# Audio_Board_REV_A.net
KiCad netlist of a schematic drawn in EAGLE
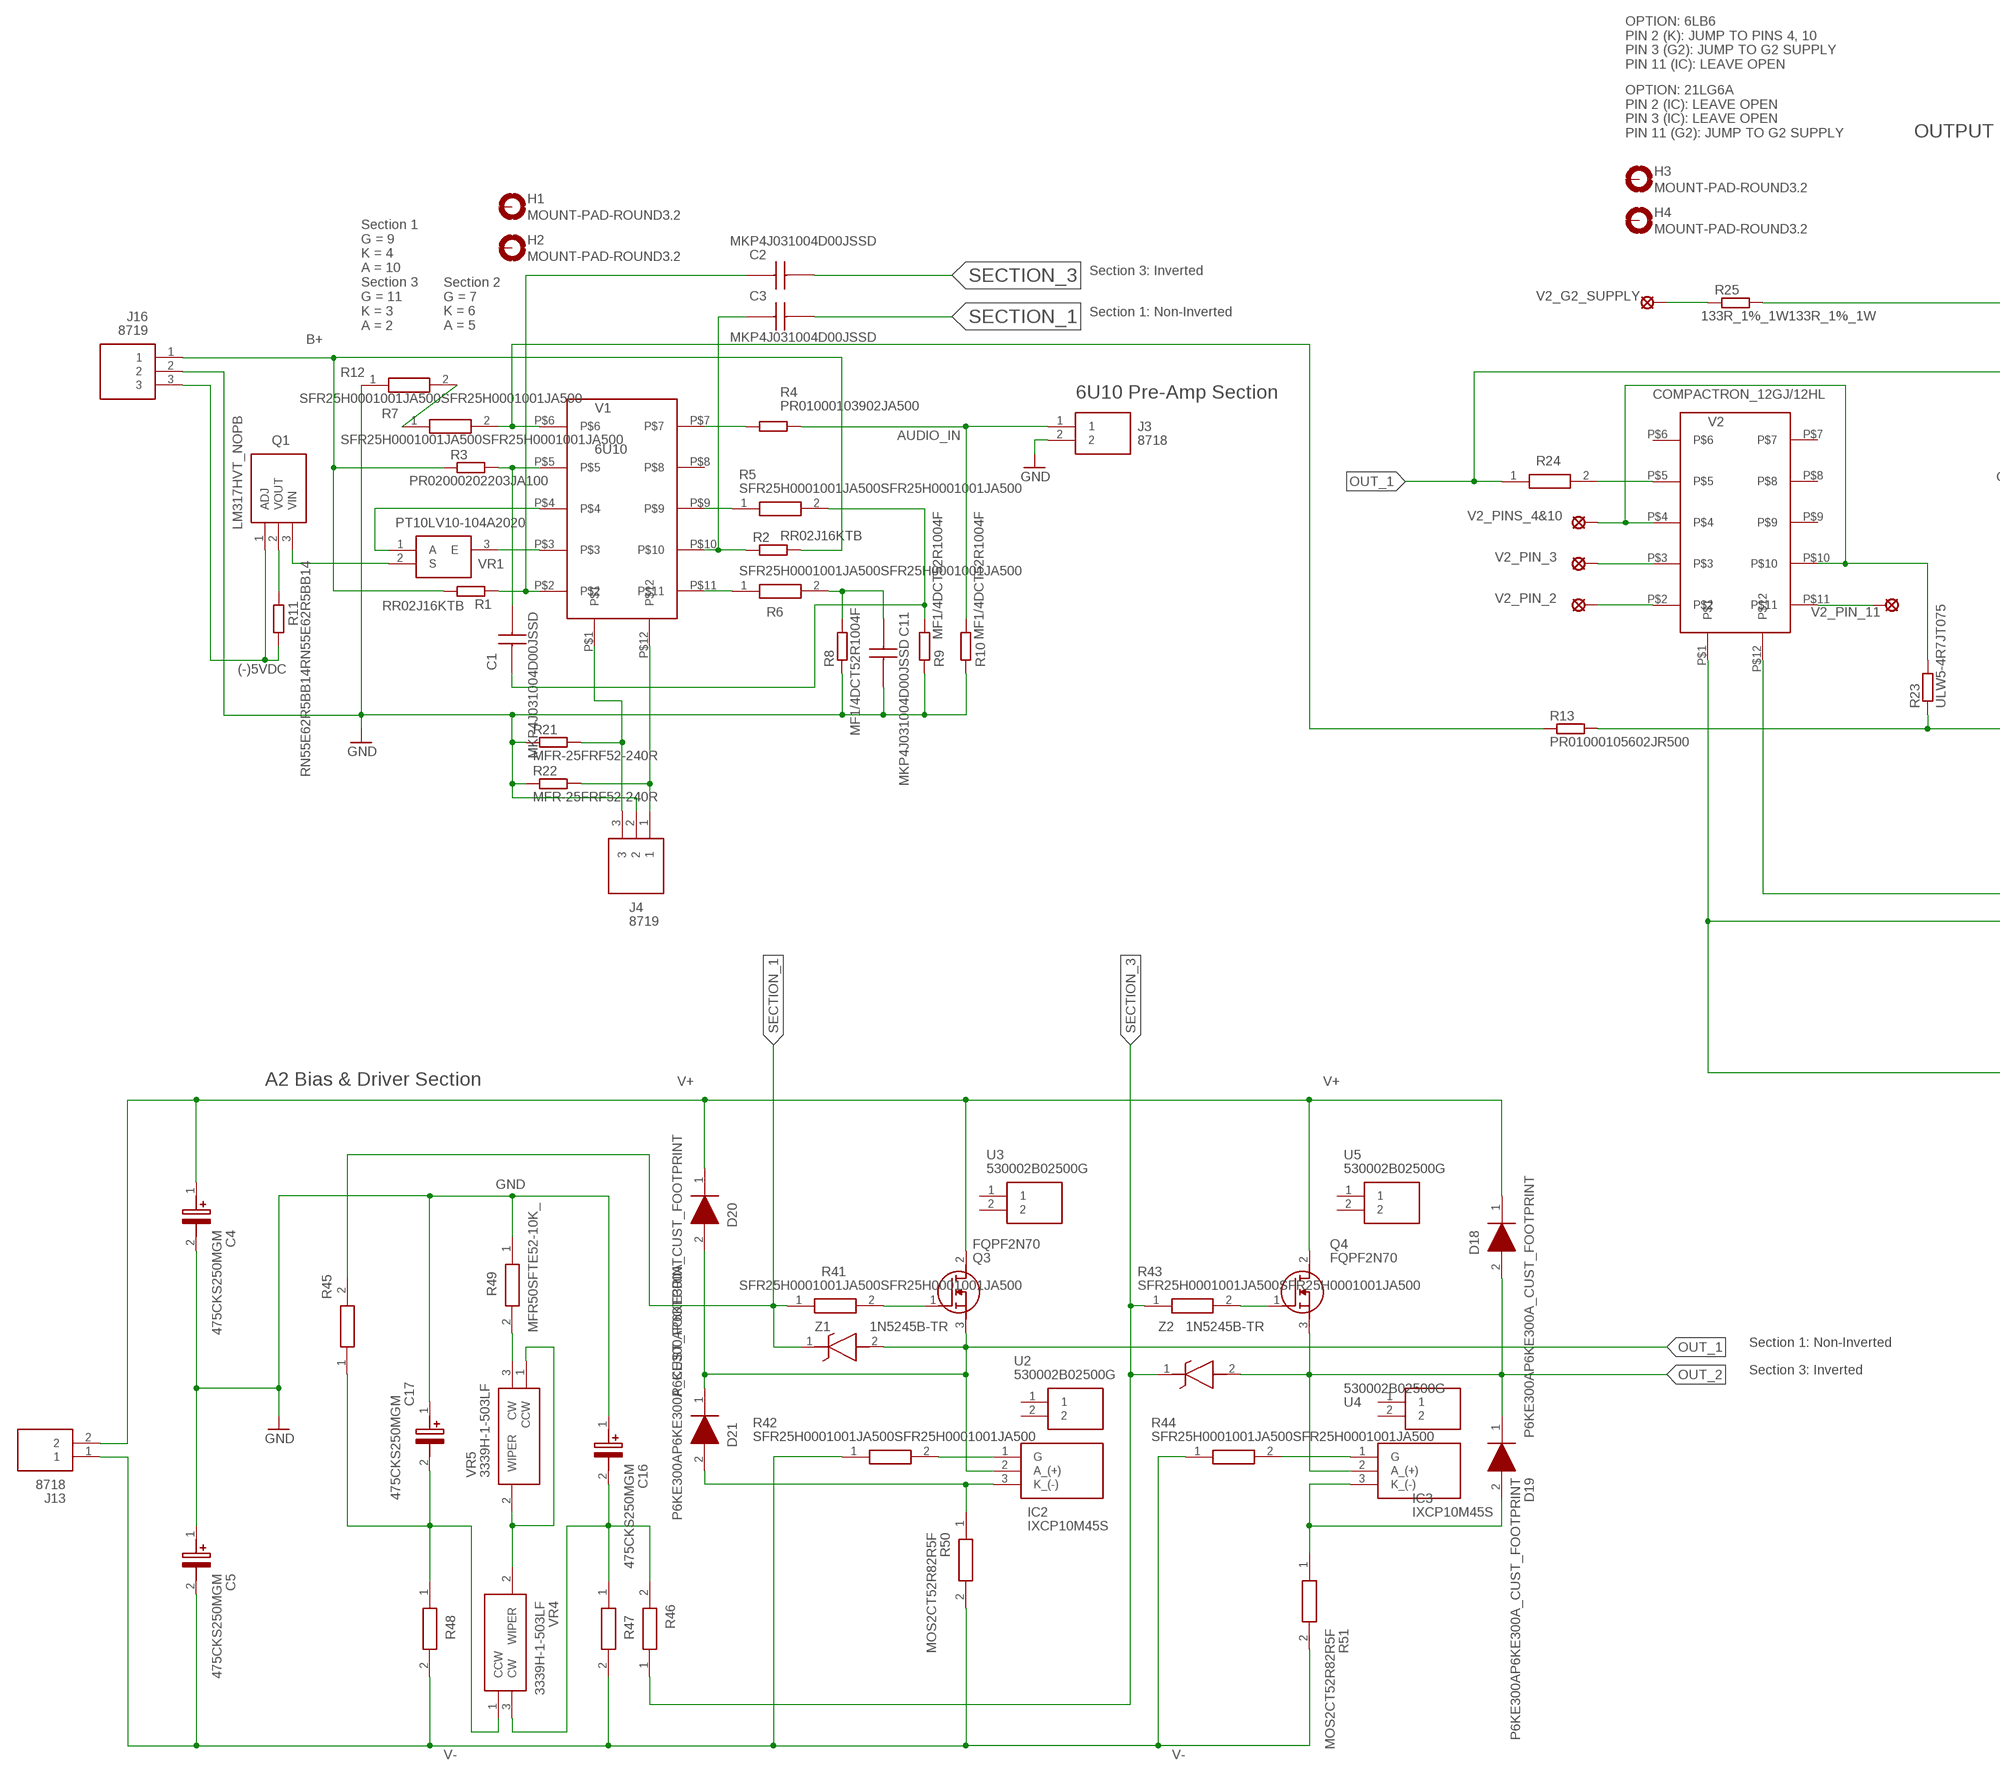
[diagram p0: schematic, sheet 1, part 1 of 2]
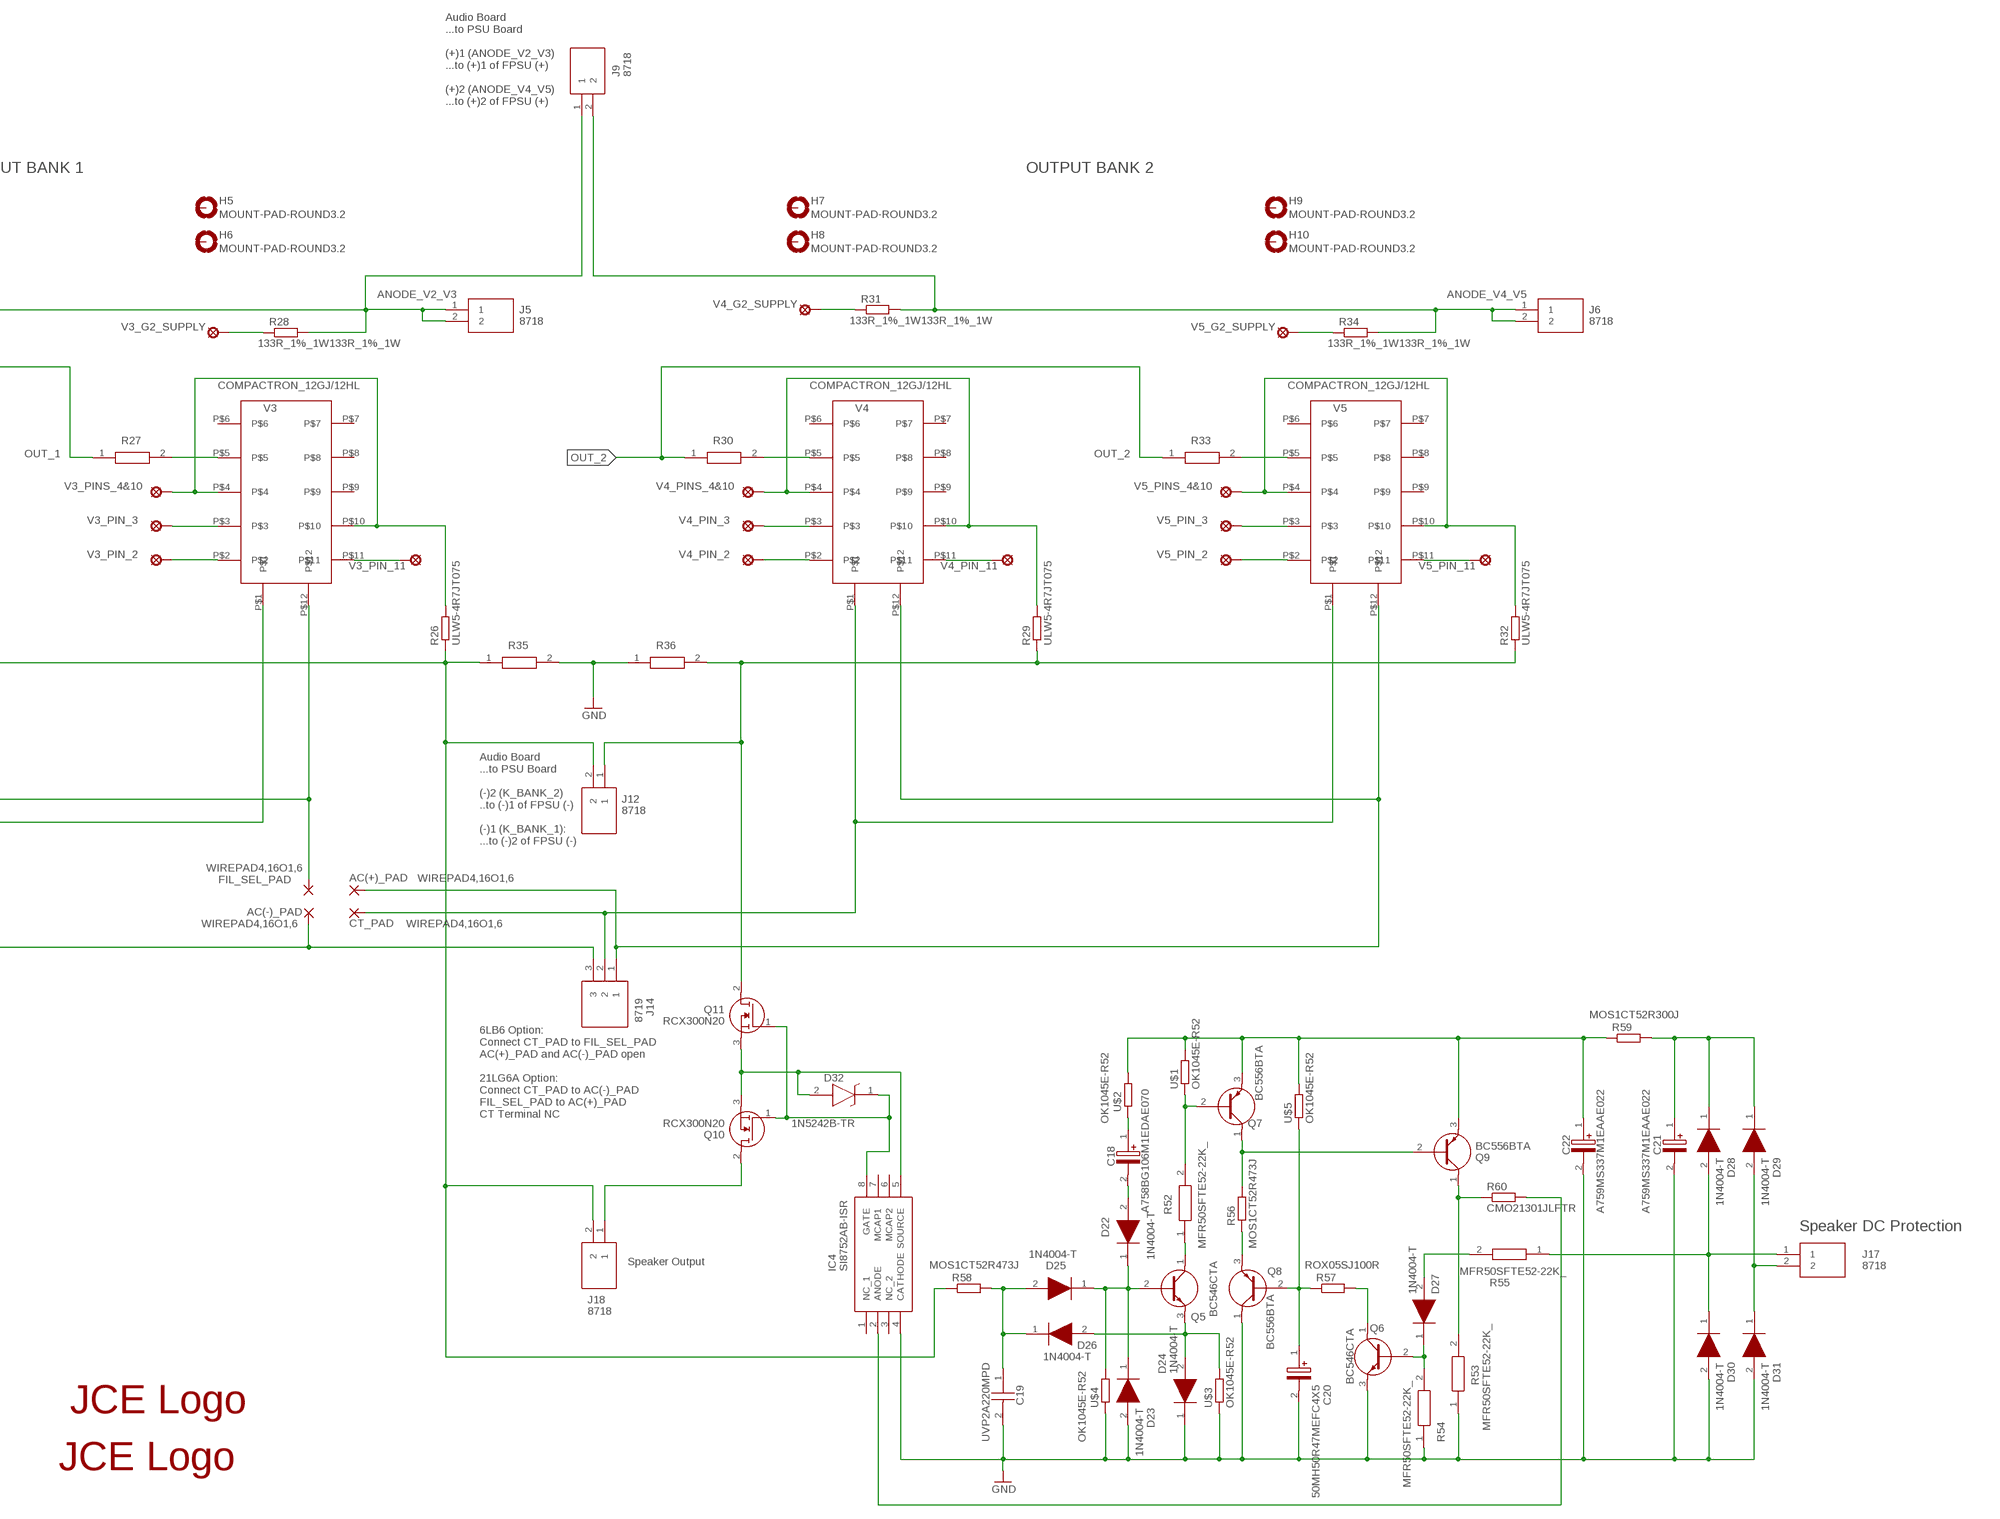
[diagram p1: schematic, sheet 1, part 2 of 2]

(export (version "E")
  (design (tool "Eeschema 10.0.6"))
  (components
    (comp (ref "AC(+)_PAD")
      (value "WIREPAD4,16O1,6")
      (footprint "eagle-import:4,16O1,6")
      (libsource (lib "eagle-import") (part "WIREPAD4,16O1,6"))
    )
    (comp (ref "AC(-)_PAD")
      (value "WIREPAD4,16O1,6")
      (footprint "eagle-import:4,16O1,6")
      (libsource (lib "eagle-import") (part "WIREPAD4,16O1,6"))
    )
    (comp (ref "C1")
      (value "MKP4J031004D00JSSD")
      (footprint "eagle-import:MKP4J031004D00_")
      (libsource (lib "eagle-import") (part "MKP4J031004D00JSSD"))
    )
    (comp (ref "C2")
      (value "MKP4J031004D00JSSD")
      (footprint "eagle-import:MKP4J031004D00_")
      (libsource (lib "eagle-import") (part "MKP4J031004D00JSSD"))
    )
    (comp (ref "C3")
      (value "MKP4J031004D00JSSD")
      (footprint "eagle-import:MKP4J031004D00_")
      (libsource (lib "eagle-import") (part "MKP4J031004D00JSSD"))
    )
    (comp (ref "C4")
      (value "475CKS250MGM")
      (footprint "eagle-import:CAPPRD250W55D655H1250")
      (libsource (lib "eagle-import") (part "475CKS250MGM"))
    )
    (comp (ref "C5")
      (value "475CKS250MGM")
      (footprint "eagle-import:CAPPRD250W55D655H1250")
      (libsource (lib "eagle-import") (part "475CKS250MGM"))
    )
    (comp (ref "C11")
      (value "MKP4J031004D00JSSD")
      (footprint "eagle-import:MKP4J031004D00_")
      (libsource (lib "eagle-import") (part "MKP4J031004D00JSSD"))
    )
    (comp (ref "C16")
      (value "475CKS250MGM")
      (footprint "eagle-import:CAPPRD250W55D655H1250")
      (libsource (lib "eagle-import") (part "475CKS250MGM"))
    )
    (comp (ref "C17")
      (value "475CKS250MGM")
      (footprint "eagle-import:CAPPRD250W55D655H1250")
      (libsource (lib "eagle-import") (part "475CKS250MGM"))
    )
    (comp (ref "C18")
      (value "A758BG106M1EDAE070")
      (footprint "eagle-import:CAPPRD200W55D500H800")
      (fields (field (name "MOUSER_PART_NUMBER") "80-A758BG106M1EDAE70"))
      (libsource (lib "eagle-import") (part "A758BG106M1EDAE070"))
    )
    (comp (ref "C19")
      (value "UVP2A220MPD")
      (footprint "eagle-import:CAPPRD500W60D1025H1750")
      (libsource (lib "eagle-import") (part "UVP2A220MPD"))
    )
    (comp (ref "C20")
      (value "50MH50R47MEFC4X5")
      (footprint "eagle-import:CAPPRD150W45D425H650")
      (libsource (lib "eagle-import") (part "50MH50R47MEFC4X5"))
    )
    (comp (ref "C21")
      (value "A759MS337M1EAAE022")
      (footprint "eagle-import:CAPPRD500W65D1000H1300")
      (libsource (lib "eagle-import") (part "A759MS337M1EAAE022"))
    )
    (comp (ref "C22")
      (value "A759MS337M1EAAE022")
      (footprint "eagle-import:CAPPRD500W65D1000H1300")
      (libsource (lib "eagle-import") (part "A759MS337M1EAAE022"))
    )
    (comp (ref "CT_PAD")
      (value "WIREPAD4,16O1,6")
      (footprint "eagle-import:4,16O1,6")
      (libsource (lib "eagle-import") (part "WIREPAD4,16O1,6"))
    )
    (comp (ref "D18")
      (value "P6KE300AP6KE300A_CUST_FOOTPRINT")
      (footprint "eagle-import:DIOAD1299W88L640D324B")
      (libsource (lib "eagle-import") (part "P6KE300AP6KE300A_CUST_FOOTPRINT"))
    )
    (comp (ref "D19")
      (value "P6KE300AP6KE300A_CUST_FOOTPRINT")
      (footprint "eagle-import:DIOAD1299W88L640D324B")
      (libsource (lib "eagle-import") (part "P6KE300AP6KE300A_CUST_FOOTPRINT"))
    )
    (comp (ref "D20")
      (value "P6KE300AP6KE300A_CUST_FOOTPRINT")
      (footprint "eagle-import:DIOAD1299W88L640D324B")
      (libsource (lib "eagle-import") (part "P6KE300AP6KE300A_CUST_FOOTPRINT"))
    )
    (comp (ref "D21")
      (value "P6KE300AP6KE300A_CUST_FOOTPRINT")
      (footprint "eagle-import:DIOAD1299W88L640D324B")
      (libsource (lib "eagle-import") (part "P6KE300AP6KE300A_CUST_FOOTPRINT"))
    )
    (comp (ref "D22")
      (value "1N4004-T")
      (footprint "eagle-import:DIOAD1408W86L464D236")
      (fields (field (name "MOUSER_PART_NUMBER") "621-1N4004"))
      (libsource (lib "eagle-import") (part "1N4004-T"))
    )
    (comp (ref "D23")
      (value "1N4004-T")
      (footprint "eagle-import:DIOAD1408W86L464D236")
      (fields (field (name "MOUSER_PART_NUMBER") "621-1N4004"))
      (libsource (lib "eagle-import") (part "1N4004-T"))
    )
    (comp (ref "D24")
      (value "1N4004-T")
      (footprint "eagle-import:DIOAD1408W86L464D236")
      (fields (field (name "MOUSER_PART_NUMBER") "621-1N4004"))
      (libsource (lib "eagle-import") (part "1N4004-T"))
    )
    (comp (ref "D25")
      (value "1N4004-T")
      (footprint "eagle-import:DIOAD1408W86L464D236")
      (fields (field (name "MOUSER_PART_NUMBER") "621-1N4004"))
      (libsource (lib "eagle-import") (part "1N4004-T"))
    )
    (comp (ref "D26")
      (value "1N4004-T")
      (footprint "eagle-import:DIOAD1408W86L464D236")
      (fields (field (name "MOUSER_PART_NUMBER") "621-1N4004"))
      (libsource (lib "eagle-import") (part "1N4004-T"))
    )
    (comp (ref "D27")
      (value "1N4004-T")
      (footprint "eagle-import:DIOAD1408W86L464D236")
      (fields (field (name "MOUSER_PART_NUMBER") "621-1N4004"))
      (libsource (lib "eagle-import") (part "1N4004-T"))
    )
    (comp (ref "D28")
      (value "1N4004-T")
      (footprint "eagle-import:DIOAD1408W86L464D236")
      (fields (field (name "MOUSER_PART_NUMBER") "621-1N4004"))
      (libsource (lib "eagle-import") (part "1N4004-T"))
    )
    (comp (ref "D29")
      (value "1N4004-T")
      (footprint "eagle-import:DIOAD1408W86L464D236")
      (fields (field (name "MOUSER_PART_NUMBER") "621-1N4004"))
      (libsource (lib "eagle-import") (part "1N4004-T"))
    )
    (comp (ref "D30")
      (value "1N4004-T")
      (footprint "eagle-import:DIOAD1408W86L464D236")
      (fields (field (name "MOUSER_PART_NUMBER") "621-1N4004"))
      (libsource (lib "eagle-import") (part "1N4004-T"))
    )
    (comp (ref "D31")
      (value "1N4004-T")
      (footprint "eagle-import:DIOAD1408W86L464D236")
      (fields (field (name "MOUSER_PART_NUMBER") "621-1N4004"))
      (libsource (lib "eagle-import") (part "1N4004-T"))
    )
    (comp (ref "D32")
      (value "1N5242B-TR")
      (footprint "eagle-import:DIOAD700W55L350D160B")
      (libsource (lib "eagle-import") (part "1N5242B-TR"))
    )
    (comp (ref "FIL_SEL_PAD")
      (value "WIREPAD4,16O1,6")
      (footprint "eagle-import:4,16O1,6")
      (libsource (lib "eagle-import") (part "WIREPAD4,16O1,6"))
    )
    (comp (ref "H1")
      (value "MOUNT-PAD-ROUND3.2")
      (footprint "eagle-import:3,2-PAD")
      (libsource (lib "eagle-import") (part "MOUNT-PAD-ROUND3.2"))
    )
    (comp (ref "H2")
      (value "MOUNT-PAD-ROUND3.2")
      (footprint "eagle-import:3,2-PAD")
      (libsource (lib "eagle-import") (part "MOUNT-PAD-ROUND3.2"))
    )
    (comp (ref "H3")
      (value "MOUNT-PAD-ROUND3.2")
      (footprint "eagle-import:3,2-PAD")
      (libsource (lib "eagle-import") (part "MOUNT-PAD-ROUND3.2"))
    )
    (comp (ref "H4")
      (value "MOUNT-PAD-ROUND3.2")
      (footprint "eagle-import:3,2-PAD")
      (libsource (lib "eagle-import") (part "MOUNT-PAD-ROUND3.2"))
    )
    (comp (ref "H5")
      (value "MOUNT-PAD-ROUND3.2")
      (footprint "eagle-import:3,2-PAD")
      (libsource (lib "eagle-import") (part "MOUNT-PAD-ROUND3.2"))
    )
    (comp (ref "H6")
      (value "MOUNT-PAD-ROUND3.2")
      (footprint "eagle-import:3,2-PAD")
      (libsource (lib "eagle-import") (part "MOUNT-PAD-ROUND3.2"))
    )
    (comp (ref "H7")
      (value "MOUNT-PAD-ROUND3.2")
      (footprint "eagle-import:3,2-PAD")
      (libsource (lib "eagle-import") (part "MOUNT-PAD-ROUND3.2"))
    )
    (comp (ref "H8")
      (value "MOUNT-PAD-ROUND3.2")
      (footprint "eagle-import:3,2-PAD")
      (libsource (lib "eagle-import") (part "MOUNT-PAD-ROUND3.2"))
    )
    (comp (ref "H9")
      (value "MOUNT-PAD-ROUND3.2")
      (footprint "eagle-import:3,2-PAD")
      (libsource (lib "eagle-import") (part "MOUNT-PAD-ROUND3.2"))
    )
    (comp (ref "H10")
      (value "MOUNT-PAD-ROUND3.2")
      (footprint "eagle-import:3,2-PAD")
      (libsource (lib "eagle-import") (part "MOUNT-PAD-ROUND3.2"))
    )
    (comp (ref "IC2")
      (value "IXCP10M45S")
      (footprint "eagle-import:TO254P482X1016X2386-3P")
      (fields (field (name "MOUSER_PART_NUMBER") "747-IXCP10M45S"))
      (libsource (lib "eagle-import") (part "IXCP10M45S"))
    )
    (comp (ref "IC3")
      (value "IXCP10M45S")
      (footprint "eagle-import:TO254P482X1016X2386-3P")
      (fields (field (name "MOUSER_PART_NUMBER") "747-IXCP10M45S"))
      (libsource (lib "eagle-import") (part "IXCP10M45S"))
    )
    (comp (ref "IC4")
      (value "SI8752AB-ISR")
      (footprint "eagle-import:SOIC127P600X175-8N")
      (fields (field (name "MOUSER_PART_NUMBER") "634-SI8752AB-ISR"))
      (libsource (lib "eagle-import") (part "SI8752AB-ISR"))
    )
    (comp (ref "J3")
      (value "8718")
      (footprint "eagle-import:SHDR2W99P0X500_1X2_1001X762X10")
      (fields (field (name "MOUSER_PART_NUMBER") "534-8718"))
      (libsource (lib "eagle-import") (part "8718"))
    )
    (comp (ref "J4")
      (value "8719")
      (footprint "eagle-import:8719")
      (fields (field (name "MOUSER_PART_NUMBER") "534-8719"))
      (libsource (lib "eagle-import") (part "8719"))
    )
    (comp (ref "J5")
      (value "8718")
      (footprint "eagle-import:SHDR2W99P0X500_1X2_1001X762X10")
      (fields (field (name "MOUSER_PART_NUMBER") "534-8718"))
      (libsource (lib "eagle-import") (part "8718"))
    )
    (comp (ref "J6")
      (value "8718")
      (footprint "eagle-import:SHDR2W99P0X500_1X2_1001X762X10")
      (fields (field (name "MOUSER_PART_NUMBER") "534-8718"))
      (libsource (lib "eagle-import") (part "8718"))
    )
    (comp (ref "J9")
      (value "8718")
      (footprint "eagle-import:SHDR2W99P0X500_1X2_1001X762X10")
      (fields (field (name "MOUSER_PART_NUMBER") "534-8718"))
      (libsource (lib "eagle-import") (part "8718"))
    )
    (comp (ref "J12")
      (value "8718")
      (footprint "eagle-import:SHDR2W99P0X500_1X2_1001X762X10")
      (fields (field (name "MOUSER_PART_NUMBER") "534-8718"))
      (libsource (lib "eagle-import") (part "8718"))
    )
    (comp (ref "J13")
      (value "8718")
      (footprint "eagle-import:SHDR2W99P0X500_1X2_1001X762X10")
      (fields (field (name "MOUSER_PART_NUMBER") "534-8718"))
      (libsource (lib "eagle-import") (part "8718"))
    )
    (comp (ref "J14")
      (value "8719")
      (footprint "eagle-import:8719")
      (fields (field (name "MOUSER_PART_NUMBER") "534-8719"))
      (libsource (lib "eagle-import") (part "8719"))
    )
    (comp (ref "J16")
      (value "8719")
      (footprint "eagle-import:8719")
      (fields (field (name "MOUSER_PART_NUMBER") "534-8719"))
      (libsource (lib "eagle-import") (part "8719"))
    )
    (comp (ref "J17")
      (value "8718")
      (footprint "eagle-import:SHDR2W99P0X500_1X2_1001X762X10")
      (fields (field (name "MOUSER_PART_NUMBER") "534-8718"))
      (libsource (lib "eagle-import") (part "8718"))
    )
    (comp (ref "J18")
      (value "8718")
      (footprint "eagle-import:SHDR2W99P0X500_1X2_1001X762X10")
      (fields (field (name "MOUSER_PART_NUMBER") "534-8718"))
      (libsource (lib "eagle-import") (part "8718"))
    )
    (comp (ref "Q1")
      (value "LM317HVT_NOPB")
      (footprint "eagle-import:TO254P470X1028X1955-3P")
      (fields
        (field (name "MANUFACTURER_PART_NUMBER") "LM317HVT/NOPB")
        (field (name "MOUSER_PART_NUMBER") "926-LM317HVT/NOPB")
      )
      (libsource (lib "eagle-import") (part "LM317HVT_NOPB"))
    )
    (comp (ref "Q3")
      (value "FQPF2N70")
      (footprint "eagle-import:TO254P490X1016X1977-3P")
      (libsource (lib "eagle-import") (part "FQPF2N70"))
    )
    (comp (ref "Q4")
      (value "FQPF2N70")
      (footprint "eagle-import:TO254P490X1016X1977-3P")
      (libsource (lib "eagle-import") (part "FQPF2N70"))
    )
    (comp (ref "Q5")
      (value "BC546CTA")
      (footprint "eagle-import:KA431AZTA")
      (fields (field (name "MOUSER_PART_NUMBER") "512-BC546CTA"))
      (libsource (lib "eagle-import") (part "BC546CTA"))
    )
    (comp (ref "Q6")
      (value "BC546CTA")
      (footprint "eagle-import:KA431AZTA")
      (fields (field (name "MOUSER_PART_NUMBER") "512-BC546CTA"))
      (libsource (lib "eagle-import") (part "BC546CTA"))
    )
    (comp (ref "Q7")
      (value "BC556BTA")
      (footprint "eagle-import:BC33740TA")
      (fields (field (name "MOUSER_PART_NUMBER") "512-BC556BTA"))
      (libsource (lib "eagle-import") (part "BC556BTA"))
    )
    (comp (ref "Q8")
      (value "BC556BTA")
      (footprint "eagle-import:BC33740TA")
      (fields (field (name "MOUSER_PART_NUMBER") "512-BC556BTA"))
      (libsource (lib "eagle-import") (part "BC556BTA"))
    )
    (comp (ref "Q9")
      (value "BC556BTA")
      (footprint "eagle-import:BC33740TA")
      (fields (field (name "MOUSER_PART_NUMBER") "512-BC556BTA"))
      (libsource (lib "eagle-import") (part "BC556BTA"))
    )
    (comp (ref "Q10")
      (value "RCX300N20")
      (footprint "eagle-import:TO254P480X1010X1760-3P")
      (libsource (lib "eagle-import") (part "RCX300N20"))
    )
    (comp (ref "Q11")
      (value "RCX300N20")
      (footprint "eagle-import:TO254P480X1010X1760-3P")
      (libsource (lib "eagle-import") (part "RCX300N20"))
    )
    (comp (ref "R1")
      (value "RR02J16KTB")
      (footprint "eagle-import:RESAD1630W90L900D350B")
      (libsource (lib "eagle-import") (part "RR02J16KTB"))
    )
    (comp (ref "R2")
      (value "RR02J16KTB")
      (footprint "eagle-import:RESAD1630W90L900D350B")
      (libsource (lib "eagle-import") (part "RR02J16KTB"))
    )
    (comp (ref "R3")
      (value "PR02000202203JA100")
      (footprint "eagle-import:RESAD1809W83L1100D390B")
      (libsource (lib "eagle-import") (part "PR02000202203JA100"))
    )
    (comp (ref "R4")
      (value "PR01000103902JA500")
      (footprint "eagle-import:RESAD976W63L650D250B")
      (libsource (lib "eagle-import") (part "PR01000103902JA500"))
    )
    (comp (ref "R5")
      (value "SFR25H0001001JA500SFR25H0001001JA500")
      (footprint "eagle-import:RESAD1076W63L700D250B")
      (libsource (lib "eagle-import") (part "SFR25H0001001JA500SFR25H0001001JA500"))
    )
    (comp (ref "R6")
      (value "SFR25H0001001JA500SFR25H0001001JA500")
      (footprint "eagle-import:RESAD1076W63L700D250B")
      (libsource (lib "eagle-import") (part "SFR25H0001001JA500SFR25H0001001JA500"))
    )
    (comp (ref "R7")
      (value "SFR25H0001001JA500SFR25H0001001JA500")
      (footprint "eagle-import:RESAD1076W63L700D250B")
      (libsource (lib "eagle-import") (part "SFR25H0001001JA500SFR25H0001001JA500"))
    )
    (comp (ref "R8")
      (value "MF1/4DCT52R1004F")
      (footprint "eagle-import:RESAD1000W60L630D230B")
      (libsource (lib "eagle-import") (part "MF1/4DCT52R1004F"))
    )
    (comp (ref "R9")
      (value "MF1/4DCT52R1004F")
      (footprint "eagle-import:RESAD1000W60L630D230B")
      (libsource (lib "eagle-import") (part "MF1/4DCT52R1004F"))
    )
    (comp (ref "R10")
      (value "MF1/4DCT52R1004F")
      (footprint "eagle-import:RESAD1000W60L630D230B")
      (libsource (lib "eagle-import") (part "MF1/4DCT52R1004F"))
    )
    (comp (ref "R11")
      (value "RN55E62R5BB14RN55E62R5BB14")
      (footprint "eagle-import:RESAD999W69L610D240B")
      (libsource (lib "eagle-import") (part "RN55E62R5BB14RN55E62R5BB14"))
    )
    (comp (ref "R12")
      (value "SFR25H0001001JA500SFR25H0001001JA500")
      (footprint "eagle-import:RESAD1076W63L700D250B")
      (libsource (lib "eagle-import") (part "SFR25H0001001JA500SFR25H0001001JA500"))
    )
    (comp (ref "R13")
      (value "PR01000105602JR500")
      (footprint "eagle-import:RESAD976W63L650D250B")
      (libsource (lib "eagle-import") (part "PR01000105602JR500"))
    )
    (comp (ref "R21")
      (value "MFR-25FRF52-240R")
      (footprint "eagle-import:RESAD1000W60L630D230B")
      (libsource (lib "eagle-import") (part "MFR-25FRF52-240R"))
    )
    (comp (ref "R22")
      (value "MFR-25FRF52-240R")
      (footprint "eagle-import:RESAD1000W60L630D230B")
      (libsource (lib "eagle-import") (part "MFR-25FRF52-240R"))
    )
    (comp (ref "R23")
      (value "ULW5-4R7JT075")
      (footprint "eagle-import:RESAD2010W80L1650D720B")
      (libsource (lib "eagle-import") (part "ULW5-4R7JT075"))
    )
    (comp (ref "R24")
      (value "SFR25H0001001JA500SFR25H0001001JA500")
      (footprint "eagle-import:RESAD1076W63L700D250B")
      (libsource (lib "eagle-import") (part "SFR25H0001001JA500SFR25H0001001JA500"))
    )
    (comp (ref "R25")
      (value "133R_1%_1W133R_1%_1W")
      (footprint "eagle-import:RESAD1560W50L1230D250B")
      (libsource (lib "eagle-import") (part "133R_1%_1W133R_1%_1W"))
    )
    (comp (ref "R26")
      (value "ULW5-4R7JT075")
      (footprint "eagle-import:RESAD2010W80L1650D720B")
      (libsource (lib "eagle-import") (part "ULW5-4R7JT075"))
    )
    (comp (ref "R27")
      (value "SFR25H0001001JA500SFR25H0001001JA500")
      (footprint "eagle-import:RESAD1076W63L700D250B")
      (libsource (lib "eagle-import") (part "SFR25H0001001JA500SFR25H0001001JA500"))
    )
    (comp (ref "R28")
      (value "133R_1%_1W133R_1%_1W")
      (footprint "eagle-import:RESAD1560W50L1230D250B")
      (libsource (lib "eagle-import") (part "133R_1%_1W133R_1%_1W"))
    )
    (comp (ref "R29")
      (value "ULW5-4R7JT075")
      (footprint "eagle-import:RESAD2010W80L1650D720B")
      (libsource (lib "eagle-import") (part "ULW5-4R7JT075"))
    )
    (comp (ref "R30")
      (value "SFR25H0001001JA500SFR25H0001001JA500")
      (footprint "eagle-import:RESAD1076W63L700D250B")
      (libsource (lib "eagle-import") (part "SFR25H0001001JA500SFR25H0001001JA500"))
    )
    (comp (ref "R31")
      (value "133R_1%_1W133R_1%_1W")
      (footprint "eagle-import:RESAD1560W50L1230D250B")
      (libsource (lib "eagle-import") (part "133R_1%_1W133R_1%_1W"))
    )
    (comp (ref "R32")
      (value "ULW5-4R7JT075")
      (footprint "eagle-import:RESAD2010W80L1650D720B")
      (libsource (lib "eagle-import") (part "ULW5-4R7JT075"))
    )
    (comp (ref "R33")
      (value "SFR25H0001001JA500SFR25H0001001JA500")
      (footprint "eagle-import:RESAD1076W63L700D250B")
      (libsource (lib "eagle-import") (part "SFR25H0001001JA500SFR25H0001001JA500"))
    )
    (comp (ref "R34")
      (value "133R_1%_1W133R_1%_1W")
      (footprint "eagle-import:RESAD1560W50L1230D250B")
      (libsource (lib "eagle-import") (part "133R_1%_1W133R_1%_1W"))
    )
    (comp (ref "R35")
      (value "SFR25H0001001JA500SFR25H0001001JA500")
      (footprint "eagle-import:RESAD1076W63L700D250B")
      (libsource (lib "eagle-import") (part "SFR25H0001001JA500SFR25H0001001JA500"))
    )
    (comp (ref "R36")
      (value "SFR25H0001001JA500SFR25H0001001JA500")
      (footprint "eagle-import:RESAD1076W63L700D250B")
      (libsource (lib "eagle-import") (part "SFR25H0001001JA500SFR25H0001001JA500"))
    )
    (comp (ref "R41")
      (value "SFR25H0001001JA500SFR25H0001001JA500")
      (footprint "eagle-import:RESAD1076W63L700D250B")
      (libsource (lib "eagle-import") (part "SFR25H0001001JA500SFR25H0001001JA500"))
    )
    (comp (ref "R42")
      (value "SFR25H0001001JA500SFR25H0001001JA500")
      (footprint "eagle-import:RESAD1076W63L700D250B")
      (libsource (lib "eagle-import") (part "SFR25H0001001JA500SFR25H0001001JA500"))
    )
    (comp (ref "R43")
      (value "SFR25H0001001JA500SFR25H0001001JA500")
      (footprint "eagle-import:RESAD1076W63L700D250B")
      (libsource (lib "eagle-import") (part "SFR25H0001001JA500SFR25H0001001JA500"))
    )
    (comp (ref "R44")
      (value "SFR25H0001001JA500SFR25H0001001JA500")
      (footprint "eagle-import:RESAD1076W63L700D250B")
      (libsource (lib "eagle-import") (part "SFR25H0001001JA500SFR25H0001001JA500"))
    )
    (comp (ref "R45")
      (value "MFR50SFTE52-220K_")
      (footprint "eagle-import:RESAD1276W63L900D330B")
      (libsource (lib "eagle-import") (part "MFR50SFTE52-220K_"))
    )
    (comp (ref "R46")
      (value "MFR50SFTE52-220K_")
      (footprint "eagle-import:RESAD1276W63L900D330B")
      (libsource (lib "eagle-import") (part "MFR50SFTE52-220K_"))
    )
    (comp (ref "R47")
      (value "MFR50SFTE52-220K_")
      (footprint "eagle-import:RESAD1276W63L900D330B")
      (libsource (lib "eagle-import") (part "MFR50SFTE52-220K_"))
    )
    (comp (ref "R48")
      (value "MFR50SFTE52-220K_")
      (footprint "eagle-import:RESAD1276W63L900D330B")
      (libsource (lib "eagle-import") (part "MFR50SFTE52-220K_"))
    )
    (comp (ref "R49")
      (value "MFR50SFTE52-10K_")
      (footprint "eagle-import:RESAD1276W63L900D330B")
      (libsource (lib "eagle-import") (part "MFR50SFTE52-10K_"))
    )
    (comp (ref "R50")
      (value "MOS2CT52R82R5F")
      (footprint "eagle-import:RESAD1660W80L1200D400B")
      (libsource (lib "eagle-import") (part "MOS2CT52R82R5F"))
    )
    (comp (ref "R51")
      (value "MOS2CT52R82R5F")
      (footprint "eagle-import:RESAD1660W80L1200D400B")
      (libsource (lib "eagle-import") (part "MOS2CT52R82R5F"))
    )
    (comp (ref "R52")
      (value "MFR50SFTE52-22K_")
      (footprint "eagle-import:RESAD1276W63L900D330B")
      (libsource (lib "eagle-import") (part "MFR50SFTE52-22K_"))
    )
    (comp (ref "R53")
      (value "MFR50SFTE52-22K_")
      (footprint "eagle-import:RESAD1276W63L900D330B")
      (libsource (lib "eagle-import") (part "MFR50SFTE52-22K_"))
    )
    (comp (ref "R54")
      (value "MFR50SFTE52-22K_")
      (footprint "eagle-import:RESAD1276W63L900D330B")
      (libsource (lib "eagle-import") (part "MFR50SFTE52-22K_"))
    )
    (comp (ref "R55")
      (value "MFR50SFTE52-22K_")
      (footprint "eagle-import:RESAD1276W63L900D330B")
      (libsource (lib "eagle-import") (part "MFR50SFTE52-22K_"))
    )
    (comp (ref "R56")
      (value "MOS1CT52R473J")
      (footprint "eagle-import:RESAD1360W80L900D300B")
      (libsource (lib "eagle-import") (part "MOS1CT52R473J"))
    )
    (comp (ref "R57")
      (value "ROX05SJ100R")
      (footprint "eagle-import:RESAD1350W75L1000D350B")
      (libsource (lib "eagle-import") (part "ROX05SJ100R"))
    )
    (comp (ref "R58")
      (value "MOS1CT52R473J")
      (footprint "eagle-import:RESAD1360W80L900D300B")
      (libsource (lib "eagle-import") (part "MOS1CT52R473J"))
    )
    (comp (ref "R59")
      (value "MOS1CT52R300J")
      (footprint "eagle-import:RESAD1360W80L900D300B")
      (libsource (lib "eagle-import") (part "MOS1CT52R300J"))
    )
    (comp (ref "R60")
      (value "CMO21301JLFTR")
      (footprint "eagle-import:ON1045E-R58")
      (libsource (lib "eagle-import") (part "CMO21301JLFTR"))
    )
    (comp (ref "SYM1")
      (value "JCE_SMALLSMALL")
      (footprint "eagle-import:JCE_SMALL")
      (libsource (lib "eagle-import") (part "JCE_SMALLSMALL"))
    )
    (comp (ref "SYM2")
      (value "JCE_SMALL")
      (footprint "eagle-import:JCE")
      (libsource (lib "eagle-import") (part "JCE_SMALL"))
    )
    (comp (ref "U$1")
      (value "OK1045E-R52")
      (footprint "eagle-import:RESAD1020W70L680D250B")
      (libsource (lib "eagle-import") (part "OK1045E-R52"))
    )
    (comp (ref "U$2")
      (value "OK1045E-R52")
      (footprint "eagle-import:RESAD1020W70L680D250B")
      (libsource (lib "eagle-import") (part "OK1045E-R52"))
    )
    (comp (ref "U$3")
      (value "OK1045E-R52")
      (footprint "eagle-import:RESAD1020W70L680D250B")
      (libsource (lib "eagle-import") (part "OK1045E-R52"))
    )
    (comp (ref "U$4")
      (value "OK1045E-R52")
      (footprint "eagle-import:RESAD1020W70L680D250B")
      (libsource (lib "eagle-import") (part "OK1045E-R52"))
    )
    (comp (ref "U$5")
      (value "OK1045E-R52")
      (footprint "eagle-import:RESAD1020W70L680D250B")
      (libsource (lib "eagle-import") (part "OK1045E-R52"))
    )
    (comp (ref "U2")
      (value "530002B02500G")
      (footprint "eagle-import:529802B02500G")
      (fields (field (name "MOUSER_PART_NUMBER") "532-530002B02500G"))
      (libsource (lib "eagle-import") (part "530002B02500G"))
    )
    (comp (ref "U3")
      (value "530002B02500G")
      (footprint "eagle-import:529802B02500G")
      (fields (field (name "MOUSER_PART_NUMBER") "532-530002B02500G"))
      (libsource (lib "eagle-import") (part "530002B02500G"))
    )
    (comp (ref "U4")
      (value "530002B02500G")
      (footprint "eagle-import:529802B02500G")
      (fields (field (name "MOUSER_PART_NUMBER") "532-530002B02500G"))
      (libsource (lib "eagle-import") (part "530002B02500G"))
    )
    (comp (ref "U5")
      (value "530002B02500G")
      (footprint "eagle-import:529802B02500G")
      (fields (field (name "MOUSER_PART_NUMBER") "532-530002B02500G"))
      (libsource (lib "eagle-import") (part "530002B02500G"))
    )
    (comp (ref "V1")
      (value "6U10")
      (footprint "eagle-import:6U10")
      (libsource (lib "eagle-import") (part "6U10"))
    )
    (comp (ref "V2")
      (value "COMPACTRON_12GJ/12HL")
      (footprint "eagle-import:6U10")
      (libsource (lib "eagle-import") (part "COMPACTRON_12GJ/12HL"))
    )
    (comp (ref "V2_G2_SUPPLY")
      (value "LSP13")
      (footprint "eagle-import:LSP13")
      (libsource (lib "eagle-import") (part "LSP13"))
    )
    (comp (ref "V2_PINS_4&10")
      (value "LSP13")
      (footprint "eagle-import:LSP13")
      (libsource (lib "eagle-import") (part "LSP13"))
    )
    (comp (ref "V2_PIN_2")
      (value "LSP13")
      (footprint "eagle-import:LSP13")
      (libsource (lib "eagle-import") (part "LSP13"))
    )
    (comp (ref "V2_PIN_3")
      (value "LSP13")
      (footprint "eagle-import:LSP13")
      (libsource (lib "eagle-import") (part "LSP13"))
    )
    (comp (ref "V2_PIN_11")
      (value "LSP13")
      (footprint "eagle-import:LSP13")
      (libsource (lib "eagle-import") (part "LSP13"))
    )
    (comp (ref "V3")
      (value "COMPACTRON_12GJ/12HL")
      (footprint "eagle-import:6U10")
      (libsource (lib "eagle-import") (part "COMPACTRON_12GJ/12HL"))
    )
    (comp (ref "V3_G2_SUPPLY")
      (value "LSP13")
      (footprint "eagle-import:LSP13")
      (libsource (lib "eagle-import") (part "LSP13"))
    )
    (comp (ref "V3_PINS_4&10")
      (value "LSP13")
      (footprint "eagle-import:LSP13")
      (libsource (lib "eagle-import") (part "LSP13"))
    )
    (comp (ref "V3_PIN_2")
      (value "LSP13")
      (footprint "eagle-import:LSP13")
      (libsource (lib "eagle-import") (part "LSP13"))
    )
    (comp (ref "V3_PIN_3")
      (value "LSP13")
      (footprint "eagle-import:LSP13")
      (libsource (lib "eagle-import") (part "LSP13"))
    )
    (comp (ref "V3_PIN_11")
      (value "LSP13")
      (footprint "eagle-import:LSP13")
      (libsource (lib "eagle-import") (part "LSP13"))
    )
    (comp (ref "V4")
      (value "COMPACTRON_12GJ/12HL")
      (footprint "eagle-import:6U10")
      (libsource (lib "eagle-import") (part "COMPACTRON_12GJ/12HL"))
    )
    (comp (ref "V4_G2_SUPPLY")
      (value "LSP13")
      (footprint "eagle-import:LSP13")
      (libsource (lib "eagle-import") (part "LSP13"))
    )
    (comp (ref "V4_PINS_4&10")
      (value "LSP13")
      (footprint "eagle-import:LSP13")
      (libsource (lib "eagle-import") (part "LSP13"))
    )
    (comp (ref "V4_PIN_2")
      (value "LSP13")
      (footprint "eagle-import:LSP13")
      (libsource (lib "eagle-import") (part "LSP13"))
    )
    (comp (ref "V4_PIN_3")
      (value "LSP13")
      (footprint "eagle-import:LSP13")
      (libsource (lib "eagle-import") (part "LSP13"))
    )
    (comp (ref "V4_PIN_11")
      (value "LSP13")
      (footprint "eagle-import:LSP13")
      (libsource (lib "eagle-import") (part "LSP13"))
    )
    (comp (ref "V5")
      (value "COMPACTRON_12GJ/12HL")
      (footprint "eagle-import:6U10")
      (libsource (lib "eagle-import") (part "COMPACTRON_12GJ/12HL"))
    )
    (comp (ref "V5_G2_SUPPLY")
      (value "LSP13")
      (footprint "eagle-import:LSP13")
      (libsource (lib "eagle-import") (part "LSP13"))
    )
    (comp (ref "V5_PINS_4&10")
      (value "LSP13")
      (footprint "eagle-import:LSP13")
      (libsource (lib "eagle-import") (part "LSP13"))
    )
    (comp (ref "V5_PIN_2")
      (value "LSP13")
      (footprint "eagle-import:LSP13")
      (libsource (lib "eagle-import") (part "LSP13"))
    )
    (comp (ref "V5_PIN_3")
      (value "LSP13")
      (footprint "eagle-import:LSP13")
      (libsource (lib "eagle-import") (part "LSP13"))
    )
    (comp (ref "V5_PIN_11")
      (value "LSP13")
      (footprint "eagle-import:LSP13")
      (libsource (lib "eagle-import") (part "LSP13"))
    )
    (comp (ref "VR1")
      (value "PT10LV10-104A2020")
      (footprint "eagle-import:PT10LV10")
      (fields
        (field (name "MANUFACTURER_PART_NUMBER") " PT10LV10-101A2020")
        (field (name "MOUSER_PART_NUMBER") "531-PT10V-100")
      )
      (libsource (lib "eagle-import") (part "PT10LV10-104A2020"))
    )
    (comp (ref "VR4")
      (value "3339H-1-503LF")
      (footprint "eagle-import:3339H1253LF")
      (fields (field (name "MOUSER_PART_NUMBER") "652-3339H-1-503LF"))
      (libsource (lib "eagle-import") (part "3339H-1-503LF"))
    )
    (comp (ref "VR5")
      (value "3339H-1-503LF")
      (footprint "eagle-import:3339H1253LF")
      (fields (field (name "MOUSER_PART_NUMBER") "652-3339H-1-503LF"))
      (libsource (lib "eagle-import") (part "3339H-1-503LF"))
    )
    (comp (ref "Z1")
      (value "1N5245B-TR")
      (footprint "eagle-import:DIOAD990W55L350D160")
      (fields (field (name "MOUSER_PART_NUMBER") "78-1N5245B"))
      (libsource (lib "eagle-import") (part "1N5245B-TR"))
    )
    (comp (ref "Z2")
      (value "1N5245B-TR")
      (footprint "eagle-import:DIOAD990W55L350D160")
      (fields (field (name "MOUSER_PART_NUMBER") "78-1N5245B"))
      (libsource (lib "eagle-import") (part "1N5245B-TR"))
    )
  )
  (nets
    (net (code "1") (name "/(-)5VDC") (class "Default")
      (node (ref "J16") (pin "3") (pinfunction "3_3") (pintype "bidirectional"))
      (node (ref "Q1") (pin "1") (pinfunction "ADJ_1") (pintype "bidirectional"))
      (node (ref "R11") (pin "1") (pinfunction "1_1") (pintype "passive"))
    )
    (net (code "2") (name "/ANODE_V2_V3") (class "Default")
      (node (ref "J5") (pin "1") (pinfunction "1_1") (pintype "bidirectional"))
      (node (ref "J5") (pin "2") (pinfunction "2_2") (pintype "bidirectional"))
      (node (ref "J9") (pin "1") (pinfunction "1_1") (pintype "bidirectional"))
      (node (ref "R25") (pin "2") (pinfunction "2_2") (pintype "passive"))
      (node (ref "R28") (pin "2") (pinfunction "2_2") (pintype "passive"))
    )
    (net (code "3") (name "/ANODE_V4_V5") (class "Default")
      (node (ref "J6") (pin "1") (pinfunction "1_1") (pintype "bidirectional"))
      (node (ref "J6") (pin "2") (pinfunction "2_2") (pintype "bidirectional"))
      (node (ref "J9") (pin "2") (pinfunction "2_2") (pintype "bidirectional"))
      (node (ref "R31") (pin "2") (pinfunction "2_2") (pintype "passive"))
      (node (ref "R34") (pin "2") (pinfunction "2_2") (pintype "passive"))
    )
    (net (code "4") (name "/AUDIO_IN") (class "Default")
      (node (ref "J3") (pin "1") (pinfunction "1_1") (pintype "bidirectional"))
      (node (ref "R10") (pin "2") (pinfunction "2_2") (pintype "passive"))
      (node (ref "R4") (pin "2") (pinfunction "2_2") (pintype "passive"))
    )
    (net (code "5") (name "/B+") (class "Default")
      (node (ref "J16") (pin "1") (pinfunction "1_1") (pintype "bidirectional"))
      (node (ref "R1") (pin "2") (pinfunction "2_2") (pintype "passive"))
      (node (ref "R2") (pin "2") (pinfunction "2_2") (pintype "passive"))
      (node (ref "R3") (pin "1") (pinfunction "1_1") (pintype "passive"))
    )
    (net (code "6") (name "/V+") (class "Default")
      (node (ref "C4") (pin "1") (pinfunction "+_1") (pintype "bidirectional"))
      (node (ref "D18") (pin "1") (pinfunction "K_1") (pintype "bidirectional"))
      (node (ref "D20") (pin "1") (pinfunction "K_1") (pintype "bidirectional"))
      (node (ref "J13") (pin "2") (pinfunction "2_2") (pintype "bidirectional"))
      (node (ref "Q3") (pin "2") (pinfunction "D_2") (pintype "power_in"))
      (node (ref "Q4") (pin "2") (pinfunction "D_2") (pintype "power_in"))
    )
    (net (code "7") (name "/V-") (class "Default")
      (node (ref "C5") (pin "2") (pinfunction "-_2") (pintype "bidirectional"))
      (node (ref "J13") (pin "1") (pinfunction "1_1") (pintype "bidirectional"))
      (node (ref "R42") (pin "1") (pinfunction "1_1") (pintype "bidirectional"))
      (node (ref "R44") (pin "1") (pinfunction "1_1") (pintype "bidirectional"))
      (node (ref "R47") (pin "2") (pinfunction "2_2") (pintype "bidirectional"))
      (node (ref "R48") (pin "2") (pinfunction "2_2") (pintype "bidirectional"))
      (node (ref "R50") (pin "2") (pinfunction "2_2") (pintype "bidirectional"))
      (node (ref "R51") (pin "2") (pinfunction "2_2") (pintype "bidirectional"))
    )
    (net (code "8") (name "GND") (class "Default")
      (node (ref "C11") (pin "P$2") (pinfunction "2_P$2") (pintype "passive"))
      (node (ref "C16") (pin "1") (pinfunction "+_1") (pintype "bidirectional"))
      (node (ref "C17") (pin "1") (pinfunction "+_1") (pintype "bidirectional"))
      (node (ref "C19") (pin "2") (pinfunction "-_2") (pintype "bidirectional"))
      (node (ref "C20") (pin "2") (pinfunction "-_2") (pintype "bidirectional"))
      (node (ref "C21") (pin "2") (pinfunction "-_2") (pintype "bidirectional"))
      (node (ref "C22") (pin "2") (pinfunction "-_2") (pintype "bidirectional"))
      (node (ref "C4") (pin "2") (pinfunction "-_2") (pintype "bidirectional"))
      (node (ref "C5") (pin "1") (pinfunction "+_1") (pintype "bidirectional"))
      (node (ref "D23") (pin "2") (pinfunction "A_2") (pintype "bidirectional"))
      (node (ref "D24") (pin "1") (pinfunction "K_1") (pintype "bidirectional"))
      (node (ref "D30") (pin "2") (pinfunction "A_2") (pintype "bidirectional"))
      (node (ref "D31") (pin "2") (pinfunction "A_2") (pintype "bidirectional"))
      (node (ref "IC4") (pin "4") (pinfunction "CATHODE_4") (pintype "bidirectional"))
      (node (ref "J16") (pin "2") (pinfunction "2_2") (pintype "bidirectional"))
      (node (ref "J3") (pin "2") (pinfunction "2_2") (pintype "bidirectional"))
      (node (ref "J4") (pin "2") (pinfunction "2_2") (pintype "bidirectional"))
      (node (ref "Q6") (pin "3") (pinfunction "E_3") (pintype "bidirectional"))
      (node (ref "Q8") (pin "1") (pinfunction "C_1") (pintype "bidirectional"))
      (node (ref "R10") (pin "1") (pinfunction "1_1") (pintype "passive"))
      (node (ref "R12") (pin "1") (pinfunction "1_1") (pintype "bidirectional"))
      (node (ref "R21") (pin "1") (pinfunction "1_1") (pintype "passive"))
      (node (ref "R22") (pin "1") (pinfunction "1_1") (pintype "passive"))
      (node (ref "R35") (pin "2") (pinfunction "2_2") (pintype "bidirectional"))
      (node (ref "R36") (pin "1") (pinfunction "1_1") (pintype "bidirectional"))
      (node (ref "R49") (pin "1") (pinfunction "1_1") (pintype "bidirectional"))
      (node (ref "R53") (pin "1") (pinfunction "1_1") (pintype "bidirectional"))
      (node (ref "R54") (pin "1") (pinfunction "1_1") (pintype "bidirectional"))
      (node (ref "R8") (pin "1") (pinfunction "1_1") (pintype "passive"))
      (node (ref "R9") (pin "1") (pinfunction "1_1") (pintype "passive"))
      (node (ref "U$3") (pin "1") (pinfunction "1_1") (pintype "passive"))
      (node (ref "U$4") (pin "1") (pinfunction "1_1") (pintype "passive"))
    )
    (net (code "9") (name "Net-(AC(+)_PAD-P)") (class "Default")
      (node (ref "AC(+)_PAD") (pin "1") (pinfunction "P_1") (pintype "passive"))
      (node (ref "J14") (pin "1") (pinfunction "1_1") (pintype "bidirectional"))
      (node (ref "V4") (pin "P$12") (pinfunction "P$12_P$12") (pintype "passive"))
      (node (ref "V5") (pin "P$12") (pinfunction "P$12_P$12") (pintype "passive"))
    )
    (net (code "10") (name "Net-(AC(-)_PAD-P)") (class "Default")
      (node (ref "AC(-)_PAD") (pin "1") (pinfunction "P_1") (pintype "passive"))
      (node (ref "J14") (pin "3") (pinfunction "3_3") (pintype "bidirectional"))
      (node (ref "V2") (pin "P$1") (pinfunction "P$1_P$1") (pintype "passive"))
      (node (ref "V3") (pin "P$1") (pinfunction "P$1_P$1") (pintype "passive"))
    )
    (net (code "11") (name "Net-(C1-1)") (class "Default")
      (node (ref "C1") (pin "P$1") (pinfunction "1_P$1") (pintype "passive"))
      (node (ref "R3") (pin "2") (pinfunction "2_2") (pintype "passive"))
      (node (ref "V1") (pin "P$5") (pinfunction "P$5_P$5") (pintype "passive"))
    )
    (net (code "12") (name "Net-(C1-2)") (class "Default")
      (node (ref "C1") (pin "P$2") (pinfunction "2_P$2") (pintype "passive"))
      (node (ref "R5") (pin "2") (pinfunction "2_2") (pintype "bidirectional"))
      (node (ref "R9") (pin "2") (pinfunction "2_2") (pintype "passive"))
    )
    (net (code "13") (name "Net-(C2-2)") (class "Default")
      (node (ref "C2") (pin "P$2") (pinfunction "2_P$2") (pintype "passive"))
      (node (ref "R1") (pin "1") (pinfunction "1_1") (pintype "passive"))
      (node (ref "V1") (pin "P$2") (pinfunction "P$2_P$2") (pintype "passive"))
    )
    (net (code "14") (name "Net-(C3-2)") (class "Default")
      (node (ref "C3") (pin "P$2") (pinfunction "2_P$2") (pintype "passive"))
      (node (ref "R2") (pin "1") (pinfunction "1_1") (pintype "passive"))
      (node (ref "V1") (pin "P$10") (pinfunction "P$10_P$10") (pintype "passive"))
    )
    (net (code "15") (name "Net-(C11-1)") (class "Default")
      (node (ref "C11") (pin "P$1") (pinfunction "1_P$1") (pintype "passive"))
      (node (ref "R6") (pin "2") (pinfunction "2_2") (pintype "bidirectional"))
      (node (ref "R8") (pin "2") (pinfunction "2_2") (pintype "passive"))
    )
    (net (code "16") (name "Net-(C16--)") (class "Default")
      (node (ref "C16") (pin "2") (pinfunction "-_2") (pintype "bidirectional"))
      (node (ref "R46") (pin "2") (pinfunction "2_2") (pintype "bidirectional"))
      (node (ref "R47") (pin "1") (pinfunction "1_1") (pintype "bidirectional"))
      (node (ref "VR4") (pin "3") (pinfunction "CW_3") (pintype "bidirectional"))
    )
    (net (code "17") (name "Net-(C17--)") (class "Default")
      (node (ref "C17") (pin "2") (pinfunction "-_2") (pintype "bidirectional"))
      (node (ref "R45") (pin "1") (pinfunction "1_1") (pintype "bidirectional"))
      (node (ref "R48") (pin "1") (pinfunction "1_1") (pintype "bidirectional"))
      (node (ref "VR4") (pin "1") (pinfunction "CCW_1") (pintype "bidirectional"))
    )
    (net (code "18") (name "Net-(C18-+)") (class "Default")
      (node (ref "C18") (pin "1") (pinfunction "+_1") (pintype "bidirectional"))
      (node (ref "U$2") (pin "1") (pinfunction "1_1") (pintype "passive"))
    )
    (net (code "19") (name "Net-(C18--)") (class "Default")
      (node (ref "C18") (pin "2") (pinfunction "-_2") (pintype "bidirectional"))
      (node (ref "D22") (pin "2") (pinfunction "A_2") (pintype "bidirectional"))
    )
    (net (code "20") (name "Net-(C19-+)") (class "Default")
      (node (ref "C19") (pin "1") (pinfunction "+_1") (pintype "bidirectional"))
      (node (ref "D25") (pin "2") (pinfunction "A_2") (pintype "bidirectional"))
      (node (ref "D26") (pin "1") (pinfunction "K_1") (pintype "bidirectional"))
      (node (ref "R58") (pin "2") (pinfunction "2_2") (pintype "passive"))
    )
    (net (code "21") (name "Net-(C20-+)") (class "Default")
      (node (ref "C20") (pin "1") (pinfunction "+_1") (pintype "bidirectional"))
      (node (ref "Q8") (pin "2") (pinfunction "B_2") (pintype "bidirectional"))
      (node (ref "R57") (pin "1") (pinfunction "1_1") (pintype "passive"))
      (node (ref "U$5") (pin "1") (pinfunction "1_1") (pintype "passive"))
    )
    (net (code "22") (name "Net-(C21-+)") (class "Default")
      (node (ref "C21") (pin "1") (pinfunction "+_1") (pintype "bidirectional"))
      (node (ref "D28") (pin "1") (pinfunction "K_1") (pintype "bidirectional"))
      (node (ref "D29") (pin "1") (pinfunction "K_1") (pintype "bidirectional"))
      (node (ref "R59") (pin "2") (pinfunction "2_2") (pintype "passive"))
    )
    (net (code "23") (name "Net-(C22-+)") (class "Default")
      (node (ref "C22") (pin "1") (pinfunction "+_1") (pintype "bidirectional"))
      (node (ref "Q7") (pin "3") (pinfunction "E_3") (pintype "bidirectional"))
      (node (ref "Q9") (pin "3") (pinfunction "E_3") (pintype "bidirectional"))
      (node (ref "R59") (pin "1") (pinfunction "1_1") (pintype "passive"))
      (node (ref "U$1") (pin "2") (pinfunction "2_2") (pintype "passive"))
      (node (ref "U$2") (pin "2") (pinfunction "2_2") (pintype "passive"))
      (node (ref "U$5") (pin "2") (pinfunction "2_2") (pintype "passive"))
    )
    (net (code "24") (name "Net-(CT_PAD-P)") (class "Default")
      (node (ref "CT_PAD") (pin "1") (pinfunction "P_1") (pintype "passive"))
      (node (ref "J14") (pin "2") (pinfunction "2_2") (pintype "bidirectional"))
      (node (ref "V4") (pin "P$1") (pinfunction "P$1_P$1") (pintype "passive"))
      (node (ref "V5") (pin "P$1") (pinfunction "P$1_P$1") (pintype "passive"))
    )
    (net (code "25") (name "Net-(D19-A)") (class "Default")
      (node (ref "D19") (pin "2") (pinfunction "A_2") (pintype "bidirectional"))
      (node (ref "IC3") (pin "3") (pinfunction "K_(-)_3") (pintype "bidirectional"))
      (node (ref "R51") (pin "1") (pinfunction "1_1") (pintype "bidirectional"))
    )
    (net (code "26") (name "Net-(D21-A)") (class "Default")
      (node (ref "D21") (pin "2") (pinfunction "A_2") (pintype "bidirectional"))
      (node (ref "IC2") (pin "3") (pinfunction "K_(-)_3") (pintype "bidirectional"))
      (node (ref "R50") (pin "1") (pinfunction "1_1") (pintype "bidirectional"))
    )
    (net (code "27") (name "Net-(D22-K)") (class "Default")
      (node (ref "D22") (pin "1") (pinfunction "K_1") (pintype "bidirectional"))
      (node (ref "D23") (pin "1") (pinfunction "K_1") (pintype "bidirectional"))
      (node (ref "D25") (pin "1") (pinfunction "K_1") (pintype "bidirectional"))
      (node (ref "Q5") (pin "2") (pinfunction "B_2") (pintype "bidirectional"))
      (node (ref "U$4") (pin "2") (pinfunction "2_2") (pintype "passive"))
    )
    (net (code "28") (name "Net-(D24-A)") (class "Default")
      (node (ref "D24") (pin "2") (pinfunction "A_2") (pintype "bidirectional"))
      (node (ref "D26") (pin "2") (pinfunction "A_2") (pintype "bidirectional"))
      (node (ref "Q5") (pin "3") (pinfunction "E_3") (pintype "bidirectional"))
      (node (ref "U$3") (pin "2") (pinfunction "2_2") (pintype "passive"))
    )
    (net (code "29") (name "Net-(D27-A)") (class "Default")
      (node (ref "D27") (pin "2") (pinfunction "A_2") (pintype "bidirectional"))
      (node (ref "R55") (pin "2") (pinfunction "2_2") (pintype "bidirectional"))
    )
    (net (code "30") (name "Net-(D27-K)") (class "Default")
      (node (ref "D27") (pin "1") (pinfunction "K_1") (pintype "bidirectional"))
      (node (ref "Q6") (pin "2") (pinfunction "B_2") (pintype "bidirectional"))
      (node (ref "R54") (pin "2") (pinfunction "2_2") (pintype "bidirectional"))
    )
    (net (code "31") (name "Net-(D28-A)") (class "Default")
      (node (ref "D28") (pin "2") (pinfunction "A_2") (pintype "bidirectional"))
      (node (ref "D30") (pin "1") (pinfunction "K_1") (pintype "bidirectional"))
      (node (ref "J17") (pin "1") (pinfunction "1_1") (pintype "bidirectional"))
      (node (ref "R55") (pin "1") (pinfunction "1_1") (pintype "bidirectional"))
    )
    (net (code "32") (name "Net-(D29-A)") (class "Default")
      (node (ref "D29") (pin "2") (pinfunction "A_2") (pintype "bidirectional"))
      (node (ref "D31") (pin "1") (pinfunction "K_1") (pintype "bidirectional"))
      (node (ref "J17") (pin "2") (pinfunction "2_2") (pintype "bidirectional"))
    )
    (net (code "33") (name "Net-(D32-A)") (class "Default")
      (node (ref "D32") (pin "2") (pinfunction "A_2") (pintype "bidirectional"))
      (node (ref "IC4") (pin "5") (pinfunction "SOURCE_5") (pintype "bidirectional"))
      (node (ref "Q10") (pin "3") (pinfunction "S_3") (pintype "bidirectional"))
      (node (ref "Q11") (pin "3") (pinfunction "S_3") (pintype "bidirectional"))
    )
    (net (code "34") (name "Net-(D32-K)") (class "Default")
      (node (ref "D32") (pin "1") (pinfunction "K_1") (pintype "bidirectional"))
      (node (ref "IC4") (pin "8") (pinfunction "GATE_8") (pintype "bidirectional"))
      (node (ref "Q10") (pin "1") (pinfunction "G_1") (pintype "bidirectional"))
      (node (ref "Q11") (pin "1") (pinfunction "G_1") (pintype "bidirectional"))
    )
    (net (code "35") (name "Net-(FIL_SEL_PAD-P)") (class "Default")
      (node (ref "FIL_SEL_PAD") (pin "1") (pinfunction "P_1") (pintype "passive"))
      (node (ref "V2") (pin "P$12") (pinfunction "P$12_P$12") (pintype "passive"))
      (node (ref "V3") (pin "P$12") (pinfunction "P$12_P$12") (pintype "passive"))
    )
    (net (code "36") (name "Net-(IC2-G)") (class "Default")
      (node (ref "IC2") (pin "1") (pinfunction "G_1") (pintype "bidirectional"))
      (node (ref "R42") (pin "2") (pinfunction "2_2") (pintype "bidirectional"))
    )
    (net (code "37") (name "Net-(IC3-G)") (class "Default")
      (node (ref "IC3") (pin "1") (pinfunction "G_1") (pintype "bidirectional"))
      (node (ref "R44") (pin "2") (pinfunction "2_2") (pintype "bidirectional"))
    )
    (net (code "38") (name "Net-(IC4-ANODE)") (class "Default")
      (node (ref "IC4") (pin "2") (pinfunction "ANODE_2") (pintype "bidirectional"))
      (node (ref "R60") (pin "2") (pinfunction "2_2") (pintype "passive"))
    )
    (net (code "39") (name "Net-(J4-Pad1)") (class "Default")
      (node (ref "J4") (pin "1") (pinfunction "1_1") (pintype "bidirectional"))
      (node (ref "R22") (pin "2") (pinfunction "2_2") (pintype "passive"))
      (node (ref "V1") (pin "P$12") (pinfunction "P$12_P$12") (pintype "passive"))
    )
    (net (code "40") (name "Net-(J4-Pad3)") (class "Default")
      (node (ref "J4") (pin "3") (pinfunction "3_3") (pintype "bidirectional"))
      (node (ref "R21") (pin "2") (pinfunction "2_2") (pintype "passive"))
      (node (ref "V1") (pin "P$1") (pinfunction "P$1_P$1") (pintype "passive"))
    )
    (net (code "41") (name "Net-(J12-Pad2)") (class "Default")
      (node (ref "J12") (pin "2") (pinfunction "2_2") (pintype "bidirectional"))
      (node (ref "J18") (pin "2") (pinfunction "2_2") (pintype "bidirectional"))
      (node (ref "R13") (pin "2") (pinfunction "2_2") (pintype "passive"))
      (node (ref "R23") (pin "1") (pinfunction "1_1") (pintype "passive"))
      (node (ref "R26") (pin "1") (pinfunction "1_1") (pintype "passive"))
      (node (ref "R35") (pin "1") (pinfunction "1_1") (pintype "bidirectional"))
      (node (ref "R58") (pin "1") (pinfunction "1_1") (pintype "passive"))
    )
    (net (code "42") (name "Net-(Q1-VIN)") (class "Default")
      (node (ref "Q1") (pin "3") (pinfunction "VIN_3") (pintype "bidirectional"))
      (node (ref "VR1") (pin "2") (pinfunction "S_2") (pintype "bidirectional"))
    )
    (net (code "43") (name "Net-(Q1-VOUT)") (class "Default")
      (node (ref "Q1") (pin "2") (pinfunction "VOUT_2") (pintype "bidirectional"))
      (node (ref "R11") (pin "2") (pinfunction "2_2") (pintype "passive"))
    )
    (net (code "44") (name "Net-(Q3-G)") (class "Default")
      (node (ref "Q3") (pin "1") (pinfunction "G_1") (pintype "input"))
      (node (ref "R41") (pin "2") (pinfunction "2_2") (pintype "bidirectional"))
    )
    (net (code "45") (name "Net-(Q4-G)") (class "Default")
      (node (ref "Q4") (pin "1") (pinfunction "G_1") (pintype "input"))
      (node (ref "R43") (pin "2") (pinfunction "2_2") (pintype "bidirectional"))
    )
    (net (code "46") (name "Net-(Q5-C)") (class "Default")
      (node (ref "Q5") (pin "1") (pinfunction "C_1") (pintype "bidirectional"))
      (node (ref "R52") (pin "1") (pinfunction "1_1") (pintype "bidirectional"))
    )
    (net (code "47") (name "Net-(Q6-C)") (class "Default")
      (node (ref "Q6") (pin "1") (pinfunction "C_1") (pintype "bidirectional"))
      (node (ref "R57") (pin "2") (pinfunction "2_2") (pintype "passive"))
    )
    (net (code "48") (name "Net-(Q7-B)") (class "Default")
      (node (ref "Q7") (pin "2") (pinfunction "B_2") (pintype "bidirectional"))
      (node (ref "R52") (pin "2") (pinfunction "2_2") (pintype "bidirectional"))
      (node (ref "U$1") (pin "1") (pinfunction "1_1") (pintype "passive"))
    )
    (net (code "49") (name "Net-(Q7-C)") (class "Default")
      (node (ref "Q7") (pin "1") (pinfunction "C_1") (pintype "bidirectional"))
      (node (ref "Q9") (pin "2") (pinfunction "B_2") (pintype "bidirectional"))
      (node (ref "R56") (pin "2") (pinfunction "2_2") (pintype "passive"))
    )
    (net (code "50") (name "Net-(Q8-E)") (class "Default")
      (node (ref "Q8") (pin "3") (pinfunction "E_3") (pintype "bidirectional"))
      (node (ref "R56") (pin "1") (pinfunction "1_1") (pintype "passive"))
    )
    (net (code "51") (name "Net-(Q9-C)") (class "Default")
      (node (ref "Q9") (pin "1") (pinfunction "C_1") (pintype "bidirectional"))
      (node (ref "R53") (pin "2") (pinfunction "2_2") (pintype "bidirectional"))
      (node (ref "R60") (pin "1") (pinfunction "1_1") (pintype "passive"))
    )
    (net (code "52") (name "Net-(Q10-D)") (class "Default")
      (node (ref "J18") (pin "1") (pinfunction "1_1") (pintype "bidirectional"))
      (node (ref "Q10") (pin "2") (pinfunction "D_2") (pintype "bidirectional"))
    )
    (net (code "53") (name "Net-(Q11-D)") (class "Default")
      (node (ref "J12") (pin "1") (pinfunction "1_1") (pintype "bidirectional"))
      (node (ref "Q11") (pin "2") (pinfunction "D_2") (pintype "bidirectional"))
      (node (ref "R29") (pin "1") (pinfunction "1_1") (pintype "passive"))
      (node (ref "R32") (pin "1") (pinfunction "1_1") (pintype "passive"))
      (node (ref "R36") (pin "2") (pinfunction "2_2") (pintype "bidirectional"))
    )
    (net (code "54") (name "Net-(R4-Pad1)") (class "Default")
      (node (ref "R4") (pin "1") (pinfunction "1_1") (pintype "passive"))
      (node (ref "V1") (pin "P$7") (pinfunction "P$7_P$7") (pintype "passive"))
    )
    (net (code "55") (name "Net-(R5-Pad1)") (class "Default")
      (node (ref "R5") (pin "1") (pinfunction "1_1") (pintype "bidirectional"))
      (node (ref "V1") (pin "P$9") (pinfunction "P$9_P$9") (pintype "passive"))
    )
    (net (code "56") (name "Net-(R6-Pad1)") (class "Default")
      (node (ref "R6") (pin "1") (pinfunction "1_1") (pintype "bidirectional"))
      (node (ref "V1") (pin "P$11") (pinfunction "P$11_P$11") (pintype "passive"))
    )
    (net (code "57") (name "Net-(R12-Pad2)") (class "Default")
      (node (ref "R12") (pin "2") (pinfunction "2_2") (pintype "bidirectional"))
      (node (ref "R7") (pin "1") (pinfunction "1_1") (pintype "bidirectional"))
    )
    (net (code "58") (name "Net-(R13-Pad1)") (class "Default")
      (node (ref "R13") (pin "1") (pinfunction "1_1") (pintype "passive"))
      (node (ref "R7") (pin "2") (pinfunction "2_2") (pintype "bidirectional"))
      (node (ref "V1") (pin "P$6") (pinfunction "P$6_P$6") (pintype "passive"))
    )
    (net (code "59") (name "Net-(R23-Pad2)") (class "Default")
      (node (ref "R23") (pin "2") (pinfunction "2_2") (pintype "passive"))
      (node (ref "V2") (pin "P$10") (pinfunction "P$10_P$10") (pintype "passive"))
      (node (ref "V2") (pin "P$4") (pinfunction "P$4_P$4") (pintype "passive"))
      (node (ref "V2_PINS_4&10") (pin "MP") (pinfunction "MP_MP") (pintype "passive"))
    )
    (net (code "60") (name "Net-(R24-Pad2)") (class "Default")
      (node (ref "R24") (pin "2") (pinfunction "2_2") (pintype "bidirectional"))
      (node (ref "V2") (pin "P$5") (pinfunction "P$5_P$5") (pintype "passive"))
    )
    (net (code "61") (name "Net-(R25-Pad1)") (class "Default")
      (node (ref "R25") (pin "1") (pinfunction "1_1") (pintype "passive"))
      (node (ref "V2_G2_SUPPLY") (pin "MP") (pinfunction "MP_MP") (pintype "passive"))
    )
    (net (code "62") (name "Net-(R26-Pad2)") (class "Default")
      (node (ref "R26") (pin "2") (pinfunction "2_2") (pintype "passive"))
      (node (ref "V3") (pin "P$10") (pinfunction "P$10_P$10") (pintype "passive"))
      (node (ref "V3") (pin "P$4") (pinfunction "P$4_P$4") (pintype "passive"))
      (node (ref "V3_PINS_4&10") (pin "MP") (pinfunction "MP_MP") (pintype "passive"))
    )
    (net (code "63") (name "Net-(R27-Pad2)") (class "Default")
      (node (ref "R27") (pin "2") (pinfunction "2_2") (pintype "bidirectional"))
      (node (ref "V3") (pin "P$5") (pinfunction "P$5_P$5") (pintype "passive"))
    )
    (net (code "64") (name "Net-(R28-Pad1)") (class "Default")
      (node (ref "R28") (pin "1") (pinfunction "1_1") (pintype "passive"))
      (node (ref "V3_G2_SUPPLY") (pin "MP") (pinfunction "MP_MP") (pintype "passive"))
    )
    (net (code "65") (name "Net-(R29-Pad2)") (class "Default")
      (node (ref "R29") (pin "2") (pinfunction "2_2") (pintype "passive"))
      (node (ref "V4") (pin "P$10") (pinfunction "P$10_P$10") (pintype "passive"))
      (node (ref "V4") (pin "P$4") (pinfunction "P$4_P$4") (pintype "passive"))
      (node (ref "V4_PINS_4&10") (pin "MP") (pinfunction "MP_MP") (pintype "passive"))
    )
    (net (code "66") (name "Net-(R30-Pad2)") (class "Default")
      (node (ref "R30") (pin "2") (pinfunction "2_2") (pintype "bidirectional"))
      (node (ref "V4") (pin "P$5") (pinfunction "P$5_P$5") (pintype "passive"))
    )
    (net (code "67") (name "Net-(R31-Pad1)") (class "Default")
      (node (ref "R31") (pin "1") (pinfunction "1_1") (pintype "passive"))
      (node (ref "V4_G2_SUPPLY") (pin "MP") (pinfunction "MP_MP") (pintype "passive"))
    )
    (net (code "68") (name "Net-(R32-Pad2)") (class "Default")
      (node (ref "R32") (pin "2") (pinfunction "2_2") (pintype "passive"))
      (node (ref "V5") (pin "P$10") (pinfunction "P$10_P$10") (pintype "passive"))
      (node (ref "V5") (pin "P$4") (pinfunction "P$4_P$4") (pintype "passive"))
      (node (ref "V5_PINS_4&10") (pin "MP") (pinfunction "MP_MP") (pintype "passive"))
    )
    (net (code "69") (name "Net-(R33-Pad2)") (class "Default")
      (node (ref "R33") (pin "2") (pinfunction "2_2") (pintype "bidirectional"))
      (node (ref "V5") (pin "P$5") (pinfunction "P$5_P$5") (pintype "passive"))
    )
    (net (code "70") (name "Net-(R34-Pad1)") (class "Default")
      (node (ref "R34") (pin "1") (pinfunction "1_1") (pintype "passive"))
      (node (ref "V5_G2_SUPPLY") (pin "MP") (pinfunction "MP_MP") (pintype "passive"))
    )
    (net (code "71") (name "Net-(V2-PadP$2)") (class "Default")
      (node (ref "V2") (pin "P$2") (pinfunction "P$2_P$2") (pintype "passive"))
      (node (ref "V2_PIN_2") (pin "MP") (pinfunction "MP_MP") (pintype "passive"))
    )
    (net (code "72") (name "Net-(V2-PadP$3)") (class "Default")
      (node (ref "V2") (pin "P$3") (pinfunction "P$3_P$3") (pintype "passive"))
      (node (ref "V2_PIN_3") (pin "MP") (pinfunction "MP_MP") (pintype "passive"))
    )
    (net (code "73") (name "Net-(V2-PadP$11)") (class "Default")
      (node (ref "V2") (pin "P$11") (pinfunction "P$11_P$11") (pintype "passive"))
      (node (ref "V2_PIN_11") (pin "MP") (pinfunction "MP_MP") (pintype "passive"))
    )
    (net (code "74") (name "Net-(V3-PadP$2)") (class "Default")
      (node (ref "V3") (pin "P$2") (pinfunction "P$2_P$2") (pintype "passive"))
      (node (ref "V3_PIN_2") (pin "MP") (pinfunction "MP_MP") (pintype "passive"))
    )
    (net (code "75") (name "Net-(V3-PadP$3)") (class "Default")
      (node (ref "V3") (pin "P$3") (pinfunction "P$3_P$3") (pintype "passive"))
      (node (ref "V3_PIN_3") (pin "MP") (pinfunction "MP_MP") (pintype "passive"))
    )
    (net (code "76") (name "Net-(V3-PadP$11)") (class "Default")
      (node (ref "V3") (pin "P$11") (pinfunction "P$11_P$11") (pintype "passive"))
      (node (ref "V3_PIN_11") (pin "MP") (pinfunction "MP_MP") (pintype "passive"))
    )
    (net (code "77") (name "Net-(V4-PadP$2)") (class "Default")
      (node (ref "V4") (pin "P$2") (pinfunction "P$2_P$2") (pintype "passive"))
      (node (ref "V4_PIN_2") (pin "MP") (pinfunction "MP_MP") (pintype "passive"))
    )
    (net (code "78") (name "Net-(V4-PadP$3)") (class "Default")
      (node (ref "V4") (pin "P$3") (pinfunction "P$3_P$3") (pintype "passive"))
      (node (ref "V4_PIN_3") (pin "MP") (pinfunction "MP_MP") (pintype "passive"))
    )
    (net (code "79") (name "Net-(V4-PadP$11)") (class "Default")
      (node (ref "V4") (pin "P$11") (pinfunction "P$11_P$11") (pintype "passive"))
      (node (ref "V4_PIN_11") (pin "MP") (pinfunction "MP_MP") (pintype "passive"))
    )
    (net (code "80") (name "Net-(V5-PadP$2)") (class "Default")
      (node (ref "V5") (pin "P$2") (pinfunction "P$2_P$2") (pintype "passive"))
      (node (ref "V5_PIN_2") (pin "MP") (pinfunction "MP_MP") (pintype "passive"))
    )
    (net (code "81") (name "Net-(V5-PadP$3)") (class "Default")
      (node (ref "V5") (pin "P$3") (pinfunction "P$3_P$3") (pintype "passive"))
      (node (ref "V5_PIN_3") (pin "MP") (pinfunction "MP_MP") (pintype "passive"))
    )
    (net (code "82") (name "Net-(V5-PadP$11)") (class "Default")
      (node (ref "V5") (pin "P$11") (pinfunction "P$11_P$11") (pintype "passive"))
      (node (ref "V5_PIN_11") (pin "MP") (pinfunction "MP_MP") (pintype "passive"))
    )
    (net (code "83") (name "Net-(VR1-A)") (class "Default")
      (node (ref "V1") (pin "P$4") (pinfunction "P$4_P$4") (pintype "passive"))
      (node (ref "VR1") (pin "1") (pinfunction "A_1") (pintype "bidirectional"))
    )
    (net (code "84") (name "Net-(VR1-E)") (class "Default")
      (node (ref "V1") (pin "P$3") (pinfunction "P$3_P$3") (pintype "passive"))
      (node (ref "VR1") (pin "3") (pinfunction "E_3") (pintype "bidirectional"))
    )
    (net (code "85") (name "Net-(VR4-WIPER)") (class "Default")
      (node (ref "VR4") (pin "2") (pinfunction "WIPER_2") (pintype "bidirectional"))
      (node (ref "VR5") (pin "1") (pinfunction "CCW_1") (pintype "bidirectional"))
      (node (ref "VR5") (pin "2") (pinfunction "WIPER_2") (pintype "bidirectional"))
    )
    (net (code "86") (name "Net-(VR5-CW)") (class "Default")
      (node (ref "R49") (pin "2") (pinfunction "2_2") (pintype "bidirectional"))
      (node (ref "VR5") (pin "3") (pinfunction "CW_3") (pintype "bidirectional"))
    )
    (net (code "87") (name "OUT_1") (class "Default")
      (node (ref "D20") (pin "2") (pinfunction "A_2") (pintype "bidirectional"))
      (node (ref "D21") (pin "1") (pinfunction "K_1") (pintype "bidirectional"))
      (node (ref "IC2") (pin "2") (pinfunction "A_(+)_2") (pintype "bidirectional"))
      (node (ref "Q3") (pin "3") (pinfunction "S_3") (pintype "power_in"))
      (node (ref "R24") (pin "1") (pinfunction "1_1") (pintype "bidirectional"))
      (node (ref "R27") (pin "1") (pinfunction "1_1") (pintype "bidirectional"))
      (node (ref "Z1") (pin "2") (pinfunction "A_2") (pintype "bidirectional"))
    )
    (net (code "88") (name "OUT_2") (class "Default")
      (node (ref "D18") (pin "2") (pinfunction "A_2") (pintype "bidirectional"))
      (node (ref "D19") (pin "1") (pinfunction "K_1") (pintype "bidirectional"))
      (node (ref "IC3") (pin "2") (pinfunction "A_(+)_2") (pintype "bidirectional"))
      (node (ref "Q4") (pin "3") (pinfunction "S_3") (pintype "power_in"))
      (node (ref "R30") (pin "1") (pinfunction "1_1") (pintype "bidirectional"))
      (node (ref "R33") (pin "1") (pinfunction "1_1") (pintype "bidirectional"))
      (node (ref "Z2") (pin "2") (pinfunction "A_2") (pintype "bidirectional"))
    )
    (net (code "89") (name "SECTION_1") (class "Default")
      (node (ref "C3") (pin "P$1") (pinfunction "1_P$1") (pintype "passive"))
      (node (ref "R41") (pin "1") (pinfunction "1_1") (pintype "bidirectional"))
      (node (ref "R45") (pin "2") (pinfunction "2_2") (pintype "bidirectional"))
      (node (ref "Z1") (pin "1") (pinfunction "K_1") (pintype "bidirectional"))
    )
    (net (code "90") (name "SECTION_3") (class "Default")
      (node (ref "C2") (pin "P$1") (pinfunction "1_P$1") (pintype "passive"))
      (node (ref "R43") (pin "1") (pinfunction "1_1") (pintype "bidirectional"))
      (node (ref "R46") (pin "1") (pinfunction "1_1") (pintype "bidirectional"))
      (node (ref "Z2") (pin "1") (pinfunction "K_1") (pintype "bidirectional"))
    )
    (net (code "91") (name "unconnected-(H1-MOUNT-PadB3,2)") (class "Default")
      (node (ref "H1") (pin "B3,2") (pinfunction "MOUNT_B3,2") (pintype "passive"))
    )
    (net (code "92") (name "unconnected-(H2-MOUNT-PadB3,2)") (class "Default")
      (node (ref "H2") (pin "B3,2") (pinfunction "MOUNT_B3,2") (pintype "passive"))
    )
    (net (code "93") (name "unconnected-(H3-MOUNT-PadB3,2)") (class "Default")
      (node (ref "H3") (pin "B3,2") (pinfunction "MOUNT_B3,2") (pintype "passive"))
    )
    (net (code "94") (name "unconnected-(H4-MOUNT-PadB3,2)") (class "Default")
      (node (ref "H4") (pin "B3,2") (pinfunction "MOUNT_B3,2") (pintype "passive"))
    )
    (net (code "95") (name "unconnected-(H5-MOUNT-PadB3,2)") (class "Default")
      (node (ref "H5") (pin "B3,2") (pinfunction "MOUNT_B3,2") (pintype "passive"))
    )
    (net (code "96") (name "unconnected-(H6-MOUNT-PadB3,2)") (class "Default")
      (node (ref "H6") (pin "B3,2") (pinfunction "MOUNT_B3,2") (pintype "passive"))
    )
    (net (code "97") (name "unconnected-(H7-MOUNT-PadB3,2)") (class "Default")
      (node (ref "H7") (pin "B3,2") (pinfunction "MOUNT_B3,2") (pintype "passive"))
    )
    (net (code "98") (name "unconnected-(H8-MOUNT-PadB3,2)") (class "Default")
      (node (ref "H8") (pin "B3,2") (pinfunction "MOUNT_B3,2") (pintype "passive"))
    )
    (net (code "99") (name "unconnected-(H9-MOUNT-PadB3,2)") (class "Default")
      (node (ref "H9") (pin "B3,2") (pinfunction "MOUNT_B3,2") (pintype "passive"))
    )
    (net (code "100") (name "unconnected-(H10-MOUNT-PadB3,2)") (class "Default")
      (node (ref "H10") (pin "B3,2") (pinfunction "MOUNT_B3,2") (pintype "passive"))
    )
    (net (code "101") (name "unconnected-(IC4-MCAP1-Pad7)") (class "Default")
      (node (ref "IC4") (pin "7") (pinfunction "MCAP1_7") (pintype "bidirectional"))
    )
    (net (code "102") (name "unconnected-(IC4-MCAP2-Pad6)") (class "Default")
      (node (ref "IC4") (pin "6") (pinfunction "MCAP2_6") (pintype "bidirectional"))
    )
    (net (code "103") (name "unconnected-(IC4-NC_1-Pad1)") (class "Default")
      (node (ref "IC4") (pin "1") (pinfunction "NC_1_1") (pintype "bidirectional"))
    )
    (net (code "104") (name "unconnected-(IC4-NC_2-Pad3)") (class "Default")
      (node (ref "IC4") (pin "3") (pinfunction "NC_2_3") (pintype "bidirectional"))
    )
    (net (code "105") (name "unconnected-(U2-Pad1)") (class "Default")
      (node (ref "U2") (pin "1") (pinfunction "1_1") (pintype "bidirectional"))
    )
    (net (code "106") (name "unconnected-(U2-Pad2)") (class "Default")
      (node (ref "U2") (pin "2") (pinfunction "2_2") (pintype "bidirectional"))
    )
    (net (code "107") (name "unconnected-(U3-Pad1)") (class "Default")
      (node (ref "U3") (pin "1") (pinfunction "1_1") (pintype "bidirectional"))
    )
    (net (code "108") (name "unconnected-(U3-Pad2)") (class "Default")
      (node (ref "U3") (pin "2") (pinfunction "2_2") (pintype "bidirectional"))
    )
    (net (code "109") (name "unconnected-(U4-Pad1)") (class "Default")
      (node (ref "U4") (pin "1") (pinfunction "1_1") (pintype "bidirectional"))
    )
    (net (code "110") (name "unconnected-(U4-Pad2)") (class "Default")
      (node (ref "U4") (pin "2") (pinfunction "2_2") (pintype "bidirectional"))
    )
    (net (code "111") (name "unconnected-(U5-Pad1)") (class "Default")
      (node (ref "U5") (pin "1") (pinfunction "1_1") (pintype "bidirectional"))
    )
    (net (code "112") (name "unconnected-(U5-Pad2)") (class "Default")
      (node (ref "U5") (pin "2") (pinfunction "2_2") (pintype "bidirectional"))
    )
    (net (code "113") (name "unconnected-(V1-PadP$8)") (class "Default")
      (node (ref "V1") (pin "P$8") (pinfunction "P$8_P$8") (pintype "no_connect"))
    )
    (net (code "114") (name "unconnected-(V2-PadP$6)") (class "Default")
      (node (ref "V2") (pin "P$6") (pinfunction "P$6_P$6") (pintype "no_connect"))
    )
    (net (code "115") (name "unconnected-(V2-PadP$7)") (class "Default")
      (node (ref "V2") (pin "P$7") (pinfunction "P$7_P$7") (pintype "no_connect"))
    )
    (net (code "116") (name "unconnected-(V2-PadP$8)") (class "Default")
      (node (ref "V2") (pin "P$8") (pinfunction "P$8_P$8") (pintype "no_connect"))
    )
    (net (code "117") (name "unconnected-(V2-PadP$9)") (class "Default")
      (node (ref "V2") (pin "P$9") (pinfunction "P$9_P$9") (pintype "no_connect"))
    )
    (net (code "118") (name "unconnected-(V3-PadP$6)") (class "Default")
      (node (ref "V3") (pin "P$6") (pinfunction "P$6_P$6") (pintype "no_connect"))
    )
    (net (code "119") (name "unconnected-(V3-PadP$7)") (class "Default")
      (node (ref "V3") (pin "P$7") (pinfunction "P$7_P$7") (pintype "no_connect"))
    )
    (net (code "120") (name "unconnected-(V3-PadP$8)") (class "Default")
      (node (ref "V3") (pin "P$8") (pinfunction "P$8_P$8") (pintype "no_connect"))
    )
    (net (code "121") (name "unconnected-(V3-PadP$9)") (class "Default")
      (node (ref "V3") (pin "P$9") (pinfunction "P$9_P$9") (pintype "no_connect"))
    )
    (net (code "122") (name "unconnected-(V4-PadP$6)") (class "Default")
      (node (ref "V4") (pin "P$6") (pinfunction "P$6_P$6") (pintype "no_connect"))
    )
    (net (code "123") (name "unconnected-(V4-PadP$7)") (class "Default")
      (node (ref "V4") (pin "P$7") (pinfunction "P$7_P$7") (pintype "no_connect"))
    )
    (net (code "124") (name "unconnected-(V4-PadP$8)") (class "Default")
      (node (ref "V4") (pin "P$8") (pinfunction "P$8_P$8") (pintype "no_connect"))
    )
    (net (code "125") (name "unconnected-(V4-PadP$9)") (class "Default")
      (node (ref "V4") (pin "P$9") (pinfunction "P$9_P$9") (pintype "no_connect"))
    )
    (net (code "126") (name "unconnected-(V5-PadP$6)") (class "Default")
      (node (ref "V5") (pin "P$6") (pinfunction "P$6_P$6") (pintype "no_connect"))
    )
    (net (code "127") (name "unconnected-(V5-PadP$7)") (class "Default")
      (node (ref "V5") (pin "P$7") (pinfunction "P$7_P$7") (pintype "no_connect"))
    )
    (net (code "128") (name "unconnected-(V5-PadP$8)") (class "Default")
      (node (ref "V5") (pin "P$8") (pinfunction "P$8_P$8") (pintype "no_connect"))
    )
    (net (code "129") (name "unconnected-(V5-PadP$9)") (class "Default")
      (node (ref "V5") (pin "P$9") (pinfunction "P$9_P$9") (pintype "no_connect"))
    )
  )
)
